# Regulators.net
KiCad netlist of a schematic drawn in Altium Designer
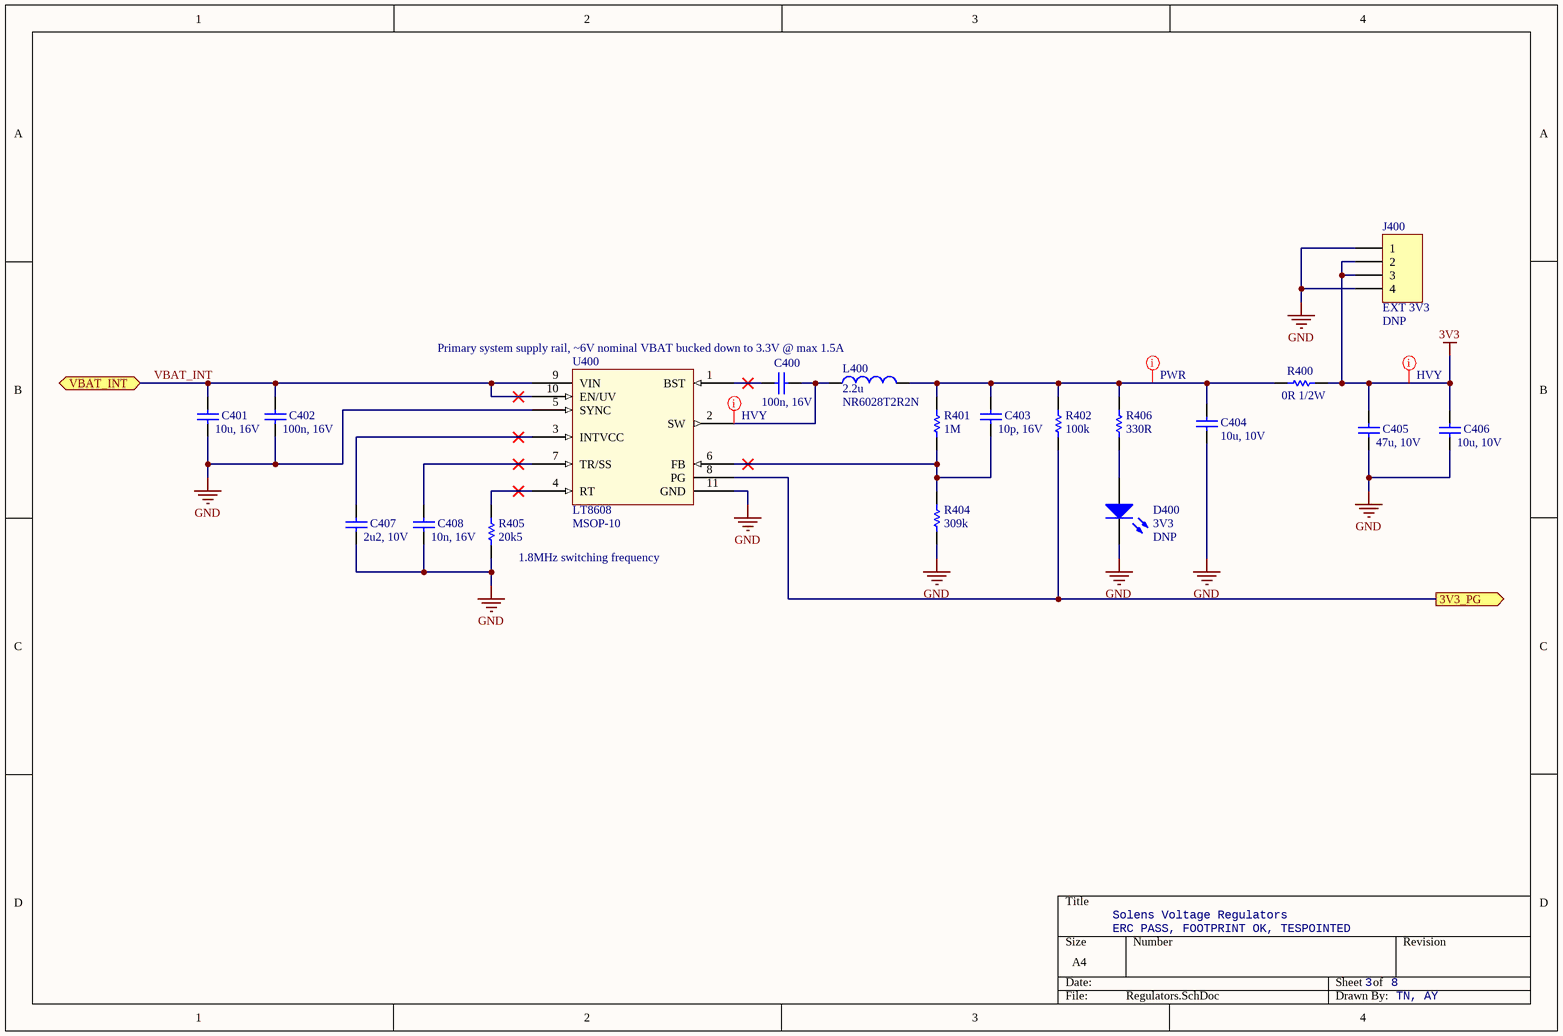
[diagram p0: Regulators.SchDoc]

(export (version "E")
  (design (tool "Eeschema 10.0.6"))
  (components
    (comp (ref "C400")
      (value "100n, 16V")
      (footprint "CAP_0402")
      (description "Capacitor")
      (fields (field (name "Comment") "100n, 16V, 0402"))
      (libsource (lib "Miscellaneous Devices") (part "Cap"))
    )
    (comp (ref "C401")
      (value "10u, 16V")
      (footprint "CAP_1206")
      (description "Capacitor")
      (fields (field (name "Comment") "10u, 16V, 1206"))
      (libsource (lib "Miscellaneous Devices") (part "Cap"))
    )
    (comp (ref "C402")
      (value "100n, 16V")
      (footprint "CAP_0402")
      (description "Capacitor")
      (fields (field (name "Comment") "100n, 16V, 0402"))
      (libsource (lib "Miscellaneous Devices") (part "Cap"))
    )
    (comp (ref "C403")
      (value "10p, 16V")
      (footprint "CAP_0805")
      (description "Capacitor")
      (fields (field (name "Comment") "10p, 16V, 0805"))
      (libsource (lib "Miscellaneous Devices") (part "Cap"))
    )
    (comp (ref "C404")
      (value "10u, 10V")
      (footprint "CAP_0805")
      (description "Capacitor")
      (fields (field (name "Comment") "10u, 10V, 0805"))
      (libsource (lib "Miscellaneous Devices") (part "Cap"))
    )
    (comp (ref "C405")
      (value "47u, 10V")
      (footprint "CAP_1206")
      (description "Capacitor")
      (fields (field (name "Comment") "47u, 10V, 1206"))
      (libsource (lib "Miscellaneous Devices") (part "Cap"))
    )
    (comp (ref "C406")
      (value "10u, 10V")
      (footprint "CAP_0805")
      (description "Capacitor")
      (fields (field (name "Comment") "10u, 10V, 0805"))
      (libsource (lib "Miscellaneous Devices") (part "Cap"))
    )
    (comp (ref "C407")
      (value "2u2, 10V")
      (footprint "CAP_0805")
      (description "Capacitor")
      (fields (field (name "Comment") "2u2, 10V, 0805"))
      (libsource (lib "Miscellaneous Devices") (part "Cap"))
    )
    (comp (ref "C408")
      (value "10n, 16V")
      (footprint "CAP_0805")
      (description "Capacitor")
      (fields (field (name "Comment") "10n, 16V, 0805"))
      (libsource (lib "Miscellaneous Devices") (part "Cap"))
    )
    (comp (ref "D400")
      (value "LED, RED, 0603 (DNP)")
      (footprint "LED_0603")
      (fields (field (name "DNP") "DNP") (field (name "FUNCTION") "3V3"))
      (libsource (lib "Miscellaneous Devices") (part "LED0"))
    )
    (comp (ref "J400")
      (value "HDR_1x4_100TH_THT (DNP)")
      (footprint "HDR1X4")
      (description "Header, 4-Pin")
      (fields (field (name "DNP") "DNP") (field (name "FUNCTION") "EXT 3V3"))
      (libsource (lib "Miscellaneous Connectors") (part "Header 4"))
    )
    (comp (ref "L400")
      (value "2.2u")
      (footprint "IND_TAIYO_NR6028")
      (description "Inductor")
      (fields (field (name "PARTNUMBER") "NR6028T2R2N") (field (name "Comment") "NR6028T2R2N"))
      (libsource (lib "Miscellaneous Devices") (part "Inductor"))
    )
    (comp (ref "R400")
      (value "0R 1/2W")
      (footprint "RES_1206")
      (description "Resistor")
      (fields (field (name "Comment") "0R, 1/2W, 1206"))
      (libsource (lib "Miscellaneous Devices") (part "Res1"))
    )
    (comp (ref "R401")
      (value "1M")
      (footprint "RES_0805")
      (description "Resistor")
      (fields (field (name "Comment") "1M, 1/8W, 0805"))
      (libsource (lib "Miscellaneous Devices") (part "Res1"))
    )
    (comp (ref "R402")
      (value "100k")
      (footprint "RES_0805")
      (description "Resistor")
      (fields (field (name "Comment") "100k, 1/8W, 0805"))
      (libsource (lib "Miscellaneous Devices") (part "Res1"))
    )
    (comp (ref "R404")
      (value "309k")
      (footprint "RES_0805")
      (description "Resistor")
      (fields (field (name "Comment") "309k, 1/8W, 0805"))
      (libsource (lib "Miscellaneous Devices") (part "Res1"))
    )
    (comp (ref "R405")
      (value "20k5")
      (footprint "RES_0805")
      (description "Resistor")
      (fields (field (name "Comment") "20k5, 1/8W, 0805"))
      (libsource (lib "Miscellaneous Devices") (part "Res1"))
    )
    (comp (ref "R406")
      (value "330R")
      (footprint "RES_0805")
      (description "Resistor")
      (fields (field (name "Comment") "330, 1/8W, 0805"))
      (libsource (lib "Miscellaneous Devices") (part "Res1"))
    )
    (comp (ref "U400")
      (value "LT8608, MSOP-10")
      (footprint "TSSOP50P490X110_HS-11N")
      (description "42V 1.5A step-down, low Iq")
      (fields (field (name "PARTNUMBER") "LT8608") (field (name "PACKAGENAME") "MSOP-10"))
      (libsource (lib "Schlib1") (part "LT8608"))
    )
  )
  (nets
    (net (code "1") (name "/3V3_PG") (class "Default")
      (node (ref "R402") (pin "1") (pinfunction "1_1") (pintype "passive"))
      (node (ref "U400") (pin "8") (pinfunction "PG_8") (pintype "open_collector"))
    )
    (net (code "2") (name "/VBAT_INT") (class "Default")
      (node (ref "C401") (pin "1") (pinfunction "1_1") (pintype "passive"))
      (node (ref "C402") (pin "1") (pinfunction "1_1") (pintype "passive"))
      (node (ref "U400") (pin "10") (pinfunction "EN/UV_10") (pintype "input"))
      (node (ref "U400") (pin "9") (pinfunction "VIN_9") (pintype "power_in"))
    )
    (net (code "3") (name "3V3") (class "Default")
      (node (ref "C405") (pin "1") (pinfunction "1_1") (pintype "passive"))
      (node (ref "C406") (pin "2") (pinfunction "2_2") (pintype "passive"))
      (node (ref "J400") (pin "2") (pinfunction "2_2") (pintype "passive"))
      (node (ref "J400") (pin "3") (pinfunction "3_3") (pintype "passive"))
      (node (ref "R400") (pin "1") (pinfunction "1_1") (pintype "passive"))
    )
    (net (code "4") (name "GND") (class "Default")
      (node (ref "C401") (pin "2") (pinfunction "2_2") (pintype "passive"))
      (node (ref "C402") (pin "2") (pinfunction "2_2") (pintype "passive"))
      (node (ref "C404") (pin "1") (pinfunction "1_1") (pintype "passive"))
      (node (ref "C405") (pin "2") (pinfunction "2_2") (pintype "passive"))
      (node (ref "C406") (pin "1") (pinfunction "1_1") (pintype "passive"))
      (node (ref "C407") (pin "2") (pinfunction "2_2") (pintype "passive"))
      (node (ref "C408") (pin "2") (pinfunction "2_2") (pintype "passive"))
      (node (ref "D400") (pin "2") (pinfunction "K_2") (pintype "passive"))
      (node (ref "J400") (pin "1") (pinfunction "1_1") (pintype "passive"))
      (node (ref "J400") (pin "4") (pinfunction "4_4") (pintype "passive"))
      (node (ref "R404") (pin "1") (pinfunction "1_1") (pintype "passive"))
      (node (ref "R405") (pin "2") (pinfunction "2_2") (pintype "passive"))
      (node (ref "U400") (pin "11") (pinfunction "GND_11") (pintype "power_in"))
      (node (ref "U400") (pin "5") (pinfunction "SYNC_5") (pintype "input"))
    )
    (net (code "5") (name "Net-(C403-Pad2)") (class "Default")
      (node (ref "C403") (pin "2") (pinfunction "2_2") (pintype "passive"))
      (node (ref "C404") (pin "2") (pinfunction "2_2") (pintype "passive"))
      (node (ref "L400") (pin "2") (pinfunction "2_2") (pintype "passive"))
      (node (ref "R400") (pin "2") (pinfunction "2_2") (pintype "passive"))
      (node (ref "R401") (pin "2") (pinfunction "2_2") (pintype "passive"))
      (node (ref "R402") (pin "2") (pinfunction "2_2") (pintype "passive"))
      (node (ref "R406") (pin "2") (pinfunction "2_2") (pintype "passive"))
    )
    (net (code "6") (name "Net-(D400-A)") (class "Default")
      (node (ref "D400") (pin "1") (pinfunction "A_1") (pintype "passive"))
      (node (ref "R406") (pin "1") (pinfunction "1_1") (pintype "passive"))
    )
    (net (code "7") (name "Net-(U400-BST)") (class "Default")
      (node (ref "C400") (pin "1") (pinfunction "1_1") (pintype "passive"))
      (node (ref "U400") (pin "1") (pinfunction "BST_1") (pintype "input"))
    )
    (net (code "8") (name "Net-(U400-FB)") (class "Default")
      (node (ref "C403") (pin "1") (pinfunction "1_1") (pintype "passive"))
      (node (ref "R401") (pin "1") (pinfunction "1_1") (pintype "passive"))
      (node (ref "R404") (pin "2") (pinfunction "2_2") (pintype "passive"))
      (node (ref "U400") (pin "6") (pinfunction "FB_6") (pintype "input"))
    )
    (net (code "9") (name "Net-(U400-INTVCC)") (class "Default")
      (node (ref "C407") (pin "1") (pinfunction "1_1") (pintype "passive"))
      (node (ref "U400") (pin "3") (pinfunction "INTVCC_3") (pintype "input"))
    )
    (net (code "10") (name "Net-(U400-RT)") (class "Default")
      (node (ref "R405") (pin "1") (pinfunction "1_1") (pintype "passive"))
      (node (ref "U400") (pin "4") (pinfunction "RT_4") (pintype "input"))
    )
    (net (code "11") (name "Net-(U400-SW)") (class "Default")
      (node (ref "C400") (pin "2") (pinfunction "2_2") (pintype "passive"))
      (node (ref "L400") (pin "1") (pinfunction "1_1") (pintype "passive"))
      (node (ref "U400") (pin "2") (pinfunction "SW_2") (pintype "output"))
    )
    (net (code "12") (name "Net-(U400-TR{slash}SS)") (class "Default")
      (node (ref "C408") (pin "1") (pinfunction "1_1") (pintype "passive"))
      (node (ref "U400") (pin "7") (pinfunction "TR/SS_7") (pintype "input"))
    )
  )
)
